# NRF9160.net
KiCad netlist of a schematic drawn in Altium Designer
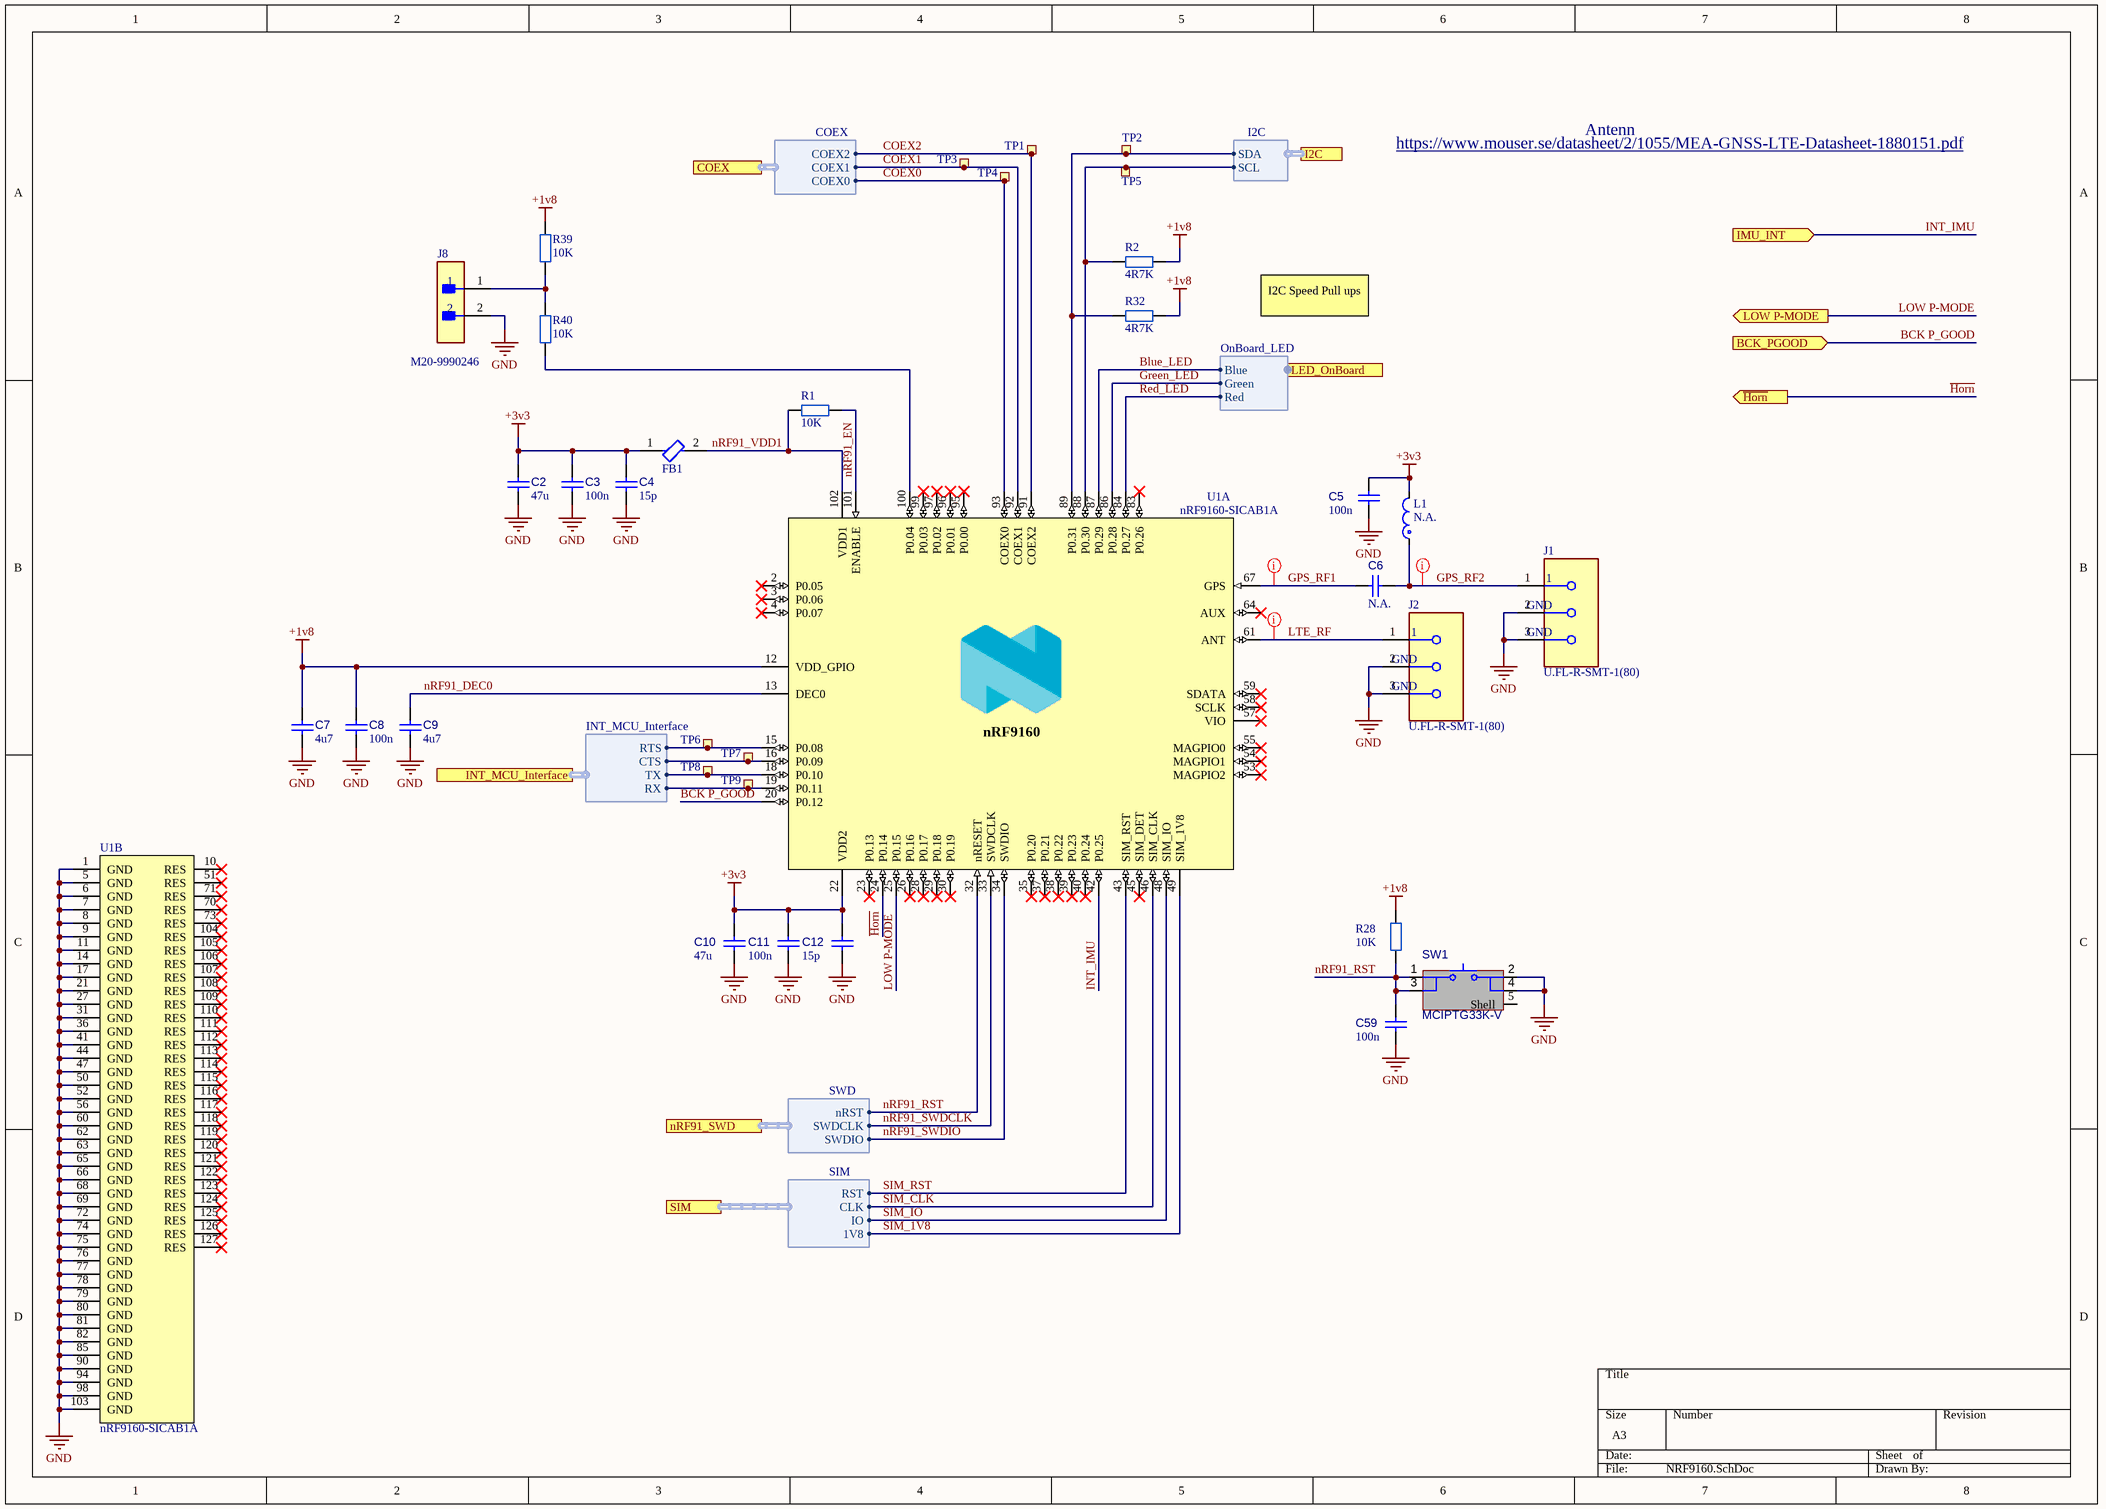
[diagram p0: NRF9160.SchDoc]

(export (version "E")
  (design (tool "Eeschema 10.0.6"))
  (components
    (comp (ref "C2")
      (value "47u")
      (footprint "CAPC2013X95X50LL10T25 HD")
      (description "Chip Capacitor, 0805 (2012 Metric)")
      (fields (field (name "TOLERANCE") "?%") (field (name "Comment") "Capacitor 0805"))
      (libsource (lib "Motonaut") (part "CAP-NP-2"))
    )
    (comp (ref "C3")
      (value "100n")
      (footprint "CAPC1005X55X25LL05T10 HD")
      (description "Chip Capacitor, 0402 (1005 Metric)")
      (fields (field (name "TOLERANCE") "?%") (field (name "Comment") "Capacitor 0402"))
      (libsource (lib "Motonaut") (part "CAP-NP-2"))
    )
    (comp (ref "C4")
      (value "15p")
      (footprint "CAPC1005X55X25LL05T10 HD")
      (description "Chip Capacitor, 0402 (1005 Metric)")
      (fields (field (name "TOLERANCE") "?%") (field (name "Comment") "Capacitor 0402"))
      (libsource (lib "Motonaut") (part "CAP-NP-2"))
    )
    (comp (ref "C5")
      (value "100n")
      (footprint "CAPC1005X55X25LL05T10 HD")
      (description "Chip Capacitor, 0402 (1005 Metric)")
      (fields (field (name "TOLERANCE") "?%") (field (name "Comment") "Capacitor 0402"))
      (libsource (lib "Motonaut") (part "CAP-NP-2"))
    )
    (comp (ref "C6")
      (value "N.A.")
      (footprint "CAPC1005X55X25LL05T10 HD")
      (description "Chip Capacitor, 0402 (1005 Metric)")
      (fields (field (name "TOLERANCE") "?%") (field (name "Comment") "Capacitor 0402"))
      (libsource (lib "Motonaut") (part "CAP-NP-2"))
    )
    (comp (ref "C7")
      (value "4u7")
      (footprint "CAPC1608X90X40LL10T20 HD")
      (description "Chip Capacitor, 0603 (1608 Metric)")
      (fields (field (name "TOLERANCE") "?%") (field (name "Comment") "Capacitor 0603"))
      (libsource (lib "Motonaut") (part "CAP-NP-2"))
    )
    (comp (ref "C8")
      (value "100n")
      (footprint "CAPC1005X55X25LL05T10 HD")
      (description "Chip Capacitor, 0402 (1005 Metric)")
      (fields (field (name "TOLERANCE") "?%") (field (name "Comment") "Capacitor 0402"))
      (libsource (lib "Motonaut") (part "CAP-NP-2"))
    )
    (comp (ref "C9")
      (value "4u7")
      (footprint "CAPC1608X90X40LL10T20 HD")
      (description "Chip Capacitor, 0603 (1608 Metric)")
      (fields (field (name "TOLERANCE") "?%") (field (name "Comment") "Capacitor 0603"))
      (libsource (lib "Motonaut") (part "CAP-NP-2"))
    )
    (comp (ref "C10")
      (value "47u")
      (footprint "CAPC2013X95X50LL10T25 HD")
      (description "Chip Capacitor, 0805 (2012 Metric)")
      (fields (field (name "TOLERANCE") "?%") (field (name "Comment") "Capacitor 0805"))
      (libsource (lib "Motonaut") (part "CAP-NP-2"))
    )
    (comp (ref "C11")
      (value "100n")
      (footprint "CAPC1005X55X25LL05T10 HD")
      (description "Chip Capacitor, 0402 (1005 Metric)")
      (fields (field (name "TOLERANCE") "?%") (field (name "Comment") "Capacitor 0402"))
      (libsource (lib "Motonaut") (part "CAP-NP-2"))
    )
    (comp (ref "C12")
      (value "15p")
      (footprint "CAPC1005X55X25LL05T10 HD")
      (description "Chip Capacitor, 0402 (1005 Metric)")
      (fields (field (name "TOLERANCE") "?%") (field (name "Comment") "Capacitor 0402"))
      (libsource (lib "Motonaut") (part "CAP-NP-2"))
    )
    (comp (ref "C59")
      (value "100n")
      (footprint "CAPC1005X55X25LL05T10 HD")
      (description "Chip Capacitor, 0402 (1005 Metric)")
      (fields (field (name "TOLERANCE") "?%") (field (name "Comment") "Capacitor 0402"))
      (libsource (lib "Motonaut") (part "CAP-NP-2"))
    )
    (comp (ref "FB1")
      (value "BLM15PX121SN1D")
      (footprint "FP-BLM15-0_05-d0_7-IPC_A")
      (description "Ferrite Beads Multi-Layer 120Ohm 25% 100MHz 2A 0.055Ohm DCR 0402 T/R")
      (libsource (lib "Motonaut") (part "5f30dd21d616792df468990f7003faa"))
    )
    (comp (ref "J1")
      (value "U.FL-R-SMT-1(80)")
      (footprint "FP-U_FL-R-SMT-1_80-MFG")
      (description "CONN U.FL RCPT STR 50 OHM SMD")
      (libsource (lib "Motonaut") (part "ad010367dc7cd7c7a13299a56582dd6"))
    )
    (comp (ref "J2")
      (value "U.FL-R-SMT-1(80)")
      (footprint "FP-U_FL-R-SMT-1_80-MFG")
      (description "CONN U.FL RCPT STR 50 OHM SMD")
      (libsource (lib "Motonaut") (part "ad010367dc7cd7c7a13299a56582dd6"))
    )
    (comp (ref "J8")
      (value "M20-9990246")
      (footprint "FP-M20-9990246-MFG")
      (description "CONN HEADER VERT 2POS 2.54MM")
      (fields
        (field (name "OCTOPART") "https://octopart.com/m20-9990246-harwin-2590635")
        (field (name "MANUFACTURER") "Harwin")
      )
      (libsource (lib "Altium Content Vault") (part "3bc925449376181038e59eaffc5286c"))
    )
    (comp (ref "L1")
      (value "N.A.")
      (footprint "INDC1005X55X25LL05T10_A")
      (description "Inductor RF Chip Thin Film 0402")
      (fields (field (name "Comment") "Inductor 0402"))
      (libsource (lib "Motonaut") (part "4cc4b267dca4c8e51f7102f422741d8"))
    )
    (comp (ref "R1")
      (value "10K")
      (footprint "RESC1005X40X25LL10T10 HD")
      (description "Resistor 0403")
      (libsource (lib "Motonaut") (part "Resistor EU"))
    )
    (comp (ref "R2")
      (value "4R7K")
      (footprint "RESC1005X40X25LL10T10 HD")
      (description "Resistor 0403")
      (libsource (lib "Motonaut") (part "Resistor EU"))
    )
    (comp (ref "R28")
      (value "10K")
      (footprint "RESC1005X40X25LL10T10 HD")
      (description "Resistor 0403")
      (libsource (lib "Motonaut") (part "Resistor EU"))
    )
    (comp (ref "R32")
      (value "4R7K")
      (footprint "RESC1005X40X25LL10T10 HD")
      (description "Resistor 0403")
      (libsource (lib "Motonaut") (part "Resistor EU"))
    )
    (comp (ref "R39")
      (value "10K")
      (footprint "RESC1005X40X25LL10T10 HD")
      (description "Resistor 0403")
      (libsource (lib "Motonaut") (part "Resistor EU"))
    )
    (comp (ref "R40")
      (value "10K")
      (footprint "RESC1005X40X25LL10T10 HD")
      (description "Resistor 0403")
      (libsource (lib "Motonaut") (part "Resistor EU"))
    )
    (comp (ref "SW1")
      (value "MCIPTG33K-V")
      (footprint "MCIPTG33K-V-Footprint-1")
      (libsource (lib "Motonaut") (part "4 pin button"))
    )
    (comp (ref "TP1")
      (value "TP_SMD_Ø0.7MM")
      (footprint "TP_SMD_Ø0.7mm")
      (description "0.7mm circular SMD testpad")
      (fields
        (field (name "MANUFACTURER") "Nordic Semiconductor")
        (field (name "MANUFACTURER PART NUMBER") "N.A.")
      )
      (libsource (lib "") (part "TP_SMD_Ø1.5MM_1"))
    )
    (comp (ref "TP2")
      (value "TP_SMD_Ø0.7MM")
      (footprint "TP_SMD_Ø0.7mm")
      (description "0.7mm circular SMD testpad")
      (fields
        (field (name "MANUFACTURER") "Nordic Semiconductor")
        (field (name "MANUFACTURER PART NUMBER") "N.A.")
      )
      (libsource (lib "") (part "TP_SMD_Ø1.5MM_1"))
    )
    (comp (ref "TP3")
      (value "TP_SMD_Ø0.7MM")
      (footprint "TP_SMD_Ø0.7mm")
      (description "0.7mm circular SMD testpad")
      (fields
        (field (name "MANUFACTURER") "Nordic Semiconductor")
        (field (name "MANUFACTURER PART NUMBER") "N.A.")
      )
      (libsource (lib "") (part "TP_SMD_Ø1.5MM_1"))
    )
    (comp (ref "TP4")
      (value "TP_SMD_Ø0.7MM")
      (footprint "TP_SMD_Ø0.7mm")
      (description "0.7mm circular SMD testpad")
      (fields
        (field (name "MANUFACTURER") "Nordic Semiconductor")
        (field (name "MANUFACTURER PART NUMBER") "N.A.")
      )
      (libsource (lib "") (part "TP_SMD_Ø1.5MM_1"))
    )
    (comp (ref "TP5")
      (value "TP_SMD_Ø0.7MM")
      (footprint "TP_SMD_Ø0.7mm")
      (description "0.7mm circular SMD testpad")
      (fields
        (field (name "MANUFACTURER") "Nordic Semiconductor")
        (field (name "MANUFACTURER PART NUMBER") "N.A.")
      )
      (libsource (lib "Motonaut") (part "TP_SMD_Ø1.5MM"))
    )
    (comp (ref "TP6")
      (value "TP_SMD_Ø0.7MM")
      (footprint "TP_SMD_Ø0.7mm")
      (description "0.7mm circular SMD testpad")
      (fields
        (field (name "MANUFACTURER") "Nordic Semiconductor")
        (field (name "MANUFACTURER PART NUMBER") "N.A.")
      )
      (libsource (lib "") (part "TP_SMD_Ø1.5MM_1"))
    )
    (comp (ref "TP7")
      (value "TP_SMD_Ø0.7MM")
      (footprint "TP_SMD_Ø0.7mm")
      (description "0.7mm circular SMD testpad")
      (fields
        (field (name "MANUFACTURER") "Nordic Semiconductor")
        (field (name "MANUFACTURER PART NUMBER") "N.A.")
      )
      (libsource (lib "") (part "TP_SMD_Ø1.5MM_1"))
    )
    (comp (ref "TP8")
      (value "TP_SMD_Ø0.7MM")
      (footprint "TP_SMD_Ø0.7mm")
      (description "0.7mm circular SMD testpad")
      (fields
        (field (name "MANUFACTURER") "Nordic Semiconductor")
        (field (name "MANUFACTURER PART NUMBER") "N.A.")
      )
      (libsource (lib "") (part "TP_SMD_Ø1.5MM_1"))
    )
    (comp (ref "TP9")
      (value "TP_SMD_Ø0.7MM")
      (footprint "TP_SMD_Ø0.7mm")
      (description "0.7mm circular SMD testpad")
      (fields
        (field (name "MANUFACTURER") "Nordic Semiconductor")
        (field (name "MANUFACTURER PART NUMBER") "N.A.")
      )
      (libsource (lib "") (part "TP_SMD_Ø1.5MM_1"))
    )
    (comp (ref "U1")
      (value "nRF9160-SICAB1A")
      (footprint "LGA50P1600X1050X104-161N")
      (description "Low power System-in-Package with integrated LTE-M/NB-IoT modem and GPS")
      (fields (field (name "MANUFACTURER") "Nordic Semiconductor"))
      (libsource (lib "Motonaut") (part "nRF9160-SICAB1A"))
    )
  )
  (nets
    (net (code "7") (name "+1v8") (class "Default")
      (node (ref "C7") (pin "2") (pinfunction "2_2") (pintype "passive"))
      (node (ref "C8") (pin "2") (pinfunction "2_2") (pintype "passive"))
      (node (ref "R2") (pin "2") (pinfunction "2_2") (pintype "passive"))
      (node (ref "R28") (pin "2") (pinfunction "2_2") (pintype "passive"))
      (node (ref "R32") (pin "2") (pinfunction "2_2") (pintype "passive"))
      (node (ref "R39") (pin "1") (pinfunction "1_1") (pintype "passive"))
      (node (ref "U1") (pin "12") (pinfunction "VDD_GPIO_12") (pintype "power_in"))
    )
    (net (code "8") (name "+3v3") (class "Default")
      (node (ref "C10") (pin "2") (pinfunction "2_2") (pintype "passive"))
      (node (ref "C11") (pin "2") (pinfunction "2_2") (pintype "passive"))
      (node (ref "C12") (pin "2") (pinfunction "2_2") (pintype "passive"))
      (node (ref "C2") (pin "2") (pinfunction "2_2") (pintype "passive"))
      (node (ref "C3") (pin "2") (pinfunction "2_2") (pintype "passive"))
      (node (ref "C4") (pin "2") (pinfunction "2_2") (pintype "passive"))
      (node (ref "C5") (pin "1") (pinfunction "1_1") (pintype "passive"))
      (node (ref "FB1") (pin "1") (pinfunction "1_1") (pintype "passive"))
      (node (ref "L1") (pin "2") (pinfunction "2_2") (pintype "passive"))
      (node (ref "U1") (pin "22") (pinfunction "VDD2_22") (pintype "power_in"))
    )
    (net (code "9") (name "/BCK P_GOOD") (class "Default")
      (node (ref "U1") (pin "20") (pinfunction "P0.12_20") (pintype "bidirectional"))
    )
    (net (code "10") (name "/Blue_LED") (class "Default")
      (node (ref "U1") (pin "87") (pinfunction "P0.29_87") (pintype "bidirectional"))
    )
    (net (code "11") (name "/COEX0") (class "Default")
      (node (ref "TP4") (pin "1") (pinfunction "1_1") (pintype "passive"))
      (node (ref "U1") (pin "93") (pinfunction "COEX0_93") (pintype "bidirectional"))
    )
    (net (code "12") (name "/COEX1") (class "Default")
      (node (ref "TP3") (pin "1") (pinfunction "1_1") (pintype "passive"))
      (node (ref "U1") (pin "92") (pinfunction "COEX1_92") (pintype "bidirectional"))
    )
    (net (code "13") (name "/COEX2") (class "Default")
      (node (ref "TP1") (pin "1") (pinfunction "1_1") (pintype "passive"))
      (node (ref "U1") (pin "91") (pinfunction "COEX2_91") (pintype "bidirectional"))
    )
    (net (code "14") (name "/GPS_RF1") (class "Default")
      (node (ref "C6") (pin "2") (pinfunction "2_2") (pintype "passive"))
      (node (ref "U1") (pin "67") (pinfunction "GPS_67") (pintype "input"))
    )
    (net (code "15") (name "/GPS_RF2") (class "Default")
      (node (ref "C6") (pin "1") (pinfunction "1_1") (pintype "passive"))
      (node (ref "J1") (pin "1") (pinfunction "1_1") (pintype "passive"))
      (node (ref "L1") (pin "1") (pinfunction "1_1") (pintype "passive"))
    )
    (net (code "16") (name "/Green_LED") (class "Default")
      (node (ref "U1") (pin "86") (pinfunction "P0.28_86") (pintype "bidirectional"))
    )
    (net (code "17") (name "/INT_IMU") (class "Default")
      (node (ref "U1") (pin "42") (pinfunction "P0.25_42") (pintype "bidirectional"))
    )
    (net (code "18") (name "/LOW P-MODE") (class "Default")
      (node (ref "U1") (pin "25") (pinfunction "P0.15_25") (pintype "bidirectional"))
    )
    (net (code "19") (name "/LTE_RF") (class "Default")
      (node (ref "J2") (pin "1") (pinfunction "1_1") (pintype "passive"))
      (node (ref "U1") (pin "61") (pinfunction "ANT_61") (pintype "bidirectional"))
    )
    (net (code "20") (name "/Red_LED") (class "Default")
      (node (ref "U1") (pin "84") (pinfunction "P0.27_84") (pintype "bidirectional"))
    )
    (net (code "21") (name "/SIM_1V8") (class "Default")
      (node (ref "U1") (pin "49") (pinfunction "SIM_1V8_49") (pintype "power_in"))
    )
    (net (code "22") (name "/SIM_CLK") (class "Default")
      (node (ref "U1") (pin "46") (pinfunction "SIM_CLK_46") (pintype "bidirectional"))
    )
    (net (code "23") (name "/SIM_IO") (class "Default")
      (node (ref "U1") (pin "48") (pinfunction "SIM_IO_48") (pintype "bidirectional"))
    )
    (net (code "24") (name "/SIM_RST") (class "Default")
      (node (ref "U1") (pin "43") (pinfunction "SIM_RST_43") (pintype "bidirectional"))
    )
    (net (code "25") (name "/nRF91_DEC0") (class "Default")
      (node (ref "C9") (pin "2") (pinfunction "2_2") (pintype "passive"))
      (node (ref "U1") (pin "13") (pinfunction "DEC0_13") (pintype "power_in"))
    )
    (net (code "26") (name "/nRF91_EN") (class "Default")
      (node (ref "R1") (pin "1") (pinfunction "1_1") (pintype "passive"))
      (node (ref "U1") (pin "101") (pinfunction "ENABLE_101") (pintype "input"))
    )
    (net (code "27") (name "/nRF91_RST") (class "Default")
      (node (ref "C59") (pin "2") (pinfunction "2_2") (pintype "passive"))
      (node (ref "R28") (pin "1") (pinfunction "1_1") (pintype "passive"))
      (node (ref "SW1") (pin "1") (pinfunction "1_1") (pintype "passive"))
      (node (ref "SW1") (pin "3") (pinfunction "3_3") (pintype "passive"))
      (node (ref "U1") (pin "32") (pinfunction "nRESET_32") (pintype "input"))
    )
    (net (code "28") (name "/nRF91_SWDCLK") (class "Default")
      (node (ref "U1") (pin "33") (pinfunction "SWDCLK_33") (pintype "input"))
    )
    (net (code "29") (name "/nRF91_SWDIO") (class "Default")
      (node (ref "U1") (pin "34") (pinfunction "SWDIO_34") (pintype "bidirectional"))
    )
    (net (code "30") (name "/nRF91_VDD1") (class "Default")
      (node (ref "FB1") (pin "2") (pinfunction "2_2") (pintype "passive"))
      (node (ref "R1") (pin "2") (pinfunction "2_2") (pintype "passive"))
      (node (ref "U1") (pin "102") (pinfunction "VDD1_102") (pintype "power_in"))
    )
    (net (code "37") (name "/~{Horn}") (class "Default")
      (node (ref "U1") (pin "24") (pinfunction "P0.14_24") (pintype "bidirectional"))
    )
    (net (code "38") (name "GND") (class "Default")
      (node (ref "C10") (pin "1") (pinfunction "1_1") (pintype "passive"))
      (node (ref "C11") (pin "1") (pinfunction "1_1") (pintype "passive"))
      (node (ref "C12") (pin "1") (pinfunction "1_1") (pintype "passive"))
      (node (ref "C2") (pin "1") (pinfunction "1_1") (pintype "passive"))
      (node (ref "C3") (pin "1") (pinfunction "1_1") (pintype "passive"))
      (node (ref "C4") (pin "1") (pinfunction "1_1") (pintype "passive"))
      (node (ref "C5") (pin "2") (pinfunction "2_2") (pintype "passive"))
      (node (ref "C59") (pin "1") (pinfunction "1_1") (pintype "passive"))
      (node (ref "C7") (pin "1") (pinfunction "1_1") (pintype "passive"))
      (node (ref "C8") (pin "1") (pinfunction "1_1") (pintype "passive"))
      (node (ref "C9") (pin "1") (pinfunction "1_1") (pintype "passive"))
      (node (ref "J1") (pin "2") (pinfunction "GND_2") (pintype "power_in"))
      (node (ref "J1") (pin "3") (pinfunction "GND_3") (pintype "power_in"))
      (node (ref "J2") (pin "2") (pinfunction "GND_2") (pintype "power_in"))
      (node (ref "J2") (pin "3") (pinfunction "GND_3") (pintype "power_in"))
      (node (ref "J8") (pin "2") (pinfunction "2_2") (pintype "passive"))
      (node (ref "SW1") (pin "2") (pinfunction "2_2") (pintype "passive"))
      (node (ref "SW1") (pin "4") (pinfunction "4_4") (pintype "passive"))
      (node (ref "U1") (pin "1") (pinfunction "GND_1") (pintype "power_in"))
      (node (ref "U1") (pin "103") (pinfunction "GND_103") (pintype "power_in"))
      (node (ref "U1") (pin "11") (pinfunction "GND_11") (pintype "passive"))
      (node (ref "U1") (pin "14") (pinfunction "GND_14") (pintype "power_in"))
      (node (ref "U1") (pin "17") (pinfunction "GND_17") (pintype "power_in"))
      (node (ref "U1") (pin "21") (pinfunction "GND_21") (pintype "power_in"))
      (node (ref "U1") (pin "27") (pinfunction "GND_27") (pintype "power_in"))
      (node (ref "U1") (pin "31") (pinfunction "GND_31") (pintype "power_in"))
      (node (ref "U1") (pin "36") (pinfunction "GND_36") (pintype "power_in"))
      (node (ref "U1") (pin "41") (pinfunction "GND_41") (pintype "power_in"))
      (node (ref "U1") (pin "44") (pinfunction "GND_44") (pintype "power_in"))
      (node (ref "U1") (pin "47") (pinfunction "GND_47") (pintype "power_in"))
      (node (ref "U1") (pin "5") (pinfunction "GND_5") (pintype "power_in"))
      (node (ref "U1") (pin "50") (pinfunction "GND_50") (pintype "power_in"))
      (node (ref "U1") (pin "52") (pinfunction "GND_52") (pintype "power_in"))
      (node (ref "U1") (pin "56") (pinfunction "GND_56") (pintype "power_in"))
      (node (ref "U1") (pin "6") (pinfunction "GND_6") (pintype "passive"))
      (node (ref "U1") (pin "60") (pinfunction "GND_60") (pintype "power_in"))
      (node (ref "U1") (pin "62") (pinfunction "GND_62") (pintype "power_in"))
      (node (ref "U1") (pin "63") (pinfunction "GND_63") (pintype "power_in"))
      (node (ref "U1") (pin "65") (pinfunction "GND_65") (pintype "power_in"))
      (node (ref "U1") (pin "66") (pinfunction "GND_66") (pintype "power_in"))
      (node (ref "U1") (pin "68") (pinfunction "GND_68") (pintype "passive"))
      (node (ref "U1") (pin "69") (pinfunction "GND_69") (pintype "passive"))
      (node (ref "U1") (pin "7") (pinfunction "GND_7") (pintype "passive"))
      (node (ref "U1") (pin "72") (pinfunction "GND_72") (pintype "power_in"))
      (node (ref "U1") (pin "74") (pinfunction "GND_74") (pintype "power_in"))
      (node (ref "U1") (pin "75") (pinfunction "GND_75") (pintype "power_in"))
      (node (ref "U1") (pin "76") (pinfunction "GND_76") (pintype "power_in"))
      (node (ref "U1") (pin "77") (pinfunction "GND_77") (pintype "power_in"))
      (node (ref "U1") (pin "78") (pinfunction "GND_78") (pintype "power_in"))
      (node (ref "U1") (pin "79") (pinfunction "GND_79") (pintype "power_in"))
      (node (ref "U1") (pin "8") (pinfunction "GND_8") (pintype "passive"))
      (node (ref "U1") (pin "80") (pinfunction "GND_80") (pintype "power_in"))
      (node (ref "U1") (pin "81") (pinfunction "GND_81") (pintype "power_in"))
      (node (ref "U1") (pin "82") (pinfunction "GND_82") (pintype "power_in"))
      (node (ref "U1") (pin "85") (pinfunction "GND_85") (pintype "power_in"))
      (node (ref "U1") (pin "9") (pinfunction "GND_9") (pintype "power_in"))
      (node (ref "U1") (pin "90") (pinfunction "GND_90") (pintype "power_in"))
      (node (ref "U1") (pin "94") (pinfunction "GND_94") (pintype "power_in"))
      (node (ref "U1") (pin "98") (pinfunction "GND_98") (pintype "power_in"))
    )
    (net (code "39") (name "Net-(J8-Pad1)") (class "Default")
      (node (ref "J8") (pin "1") (pinfunction "1_1") (pintype "passive"))
      (node (ref "R39") (pin "2") (pinfunction "2_2") (pintype "passive"))
      (node (ref "R40") (pin "2") (pinfunction "2_2") (pintype "passive"))
    )
    (net (code "40") (name "Net-(U1A-P0.04)") (class "Default")
      (node (ref "R40") (pin "1") (pinfunction "1_1") (pintype "passive"))
      (node (ref "U1") (pin "100") (pinfunction "P0.04_100") (pintype "bidirectional"))
    )
    (net (code "41") (name "Net-(U1A-P0.08)") (class "Default")
      (node (ref "TP6") (pin "1") (pinfunction "1_1") (pintype "passive"))
      (node (ref "U1") (pin "15") (pinfunction "P0.08_15") (pintype "bidirectional"))
    )
    (net (code "42") (name "Net-(U1A-P0.09)") (class "Default")
      (node (ref "TP7") (pin "1") (pinfunction "1_1") (pintype "passive"))
      (node (ref "U1") (pin "16") (pinfunction "P0.09_16") (pintype "bidirectional"))
    )
    (net (code "43") (name "Net-(U1A-P0.10)") (class "Default")
      (node (ref "TP8") (pin "1") (pinfunction "1_1") (pintype "passive"))
      (node (ref "U1") (pin "18") (pinfunction "P0.10_18") (pintype "bidirectional"))
    )
    (net (code "44") (name "Net-(U1A-P0.11)") (class "Default")
      (node (ref "TP9") (pin "1") (pinfunction "1_1") (pintype "passive"))
      (node (ref "U1") (pin "19") (pinfunction "P0.11_19") (pintype "bidirectional"))
    )
    (net (code "45") (name "Net-(U1A-P0.30)") (class "Default")
      (node (ref "R2") (pin "1") (pinfunction "1_1") (pintype "passive"))
      (node (ref "TP5") (pin "1") (pinfunction "1_1") (pintype "passive"))
      (node (ref "U1") (pin "88") (pinfunction "P0.30_88") (pintype "bidirectional"))
    )
    (net (code "46") (name "Net-(U1A-P0.31)") (class "Default")
      (node (ref "R32") (pin "1") (pinfunction "1_1") (pintype "passive"))
      (node (ref "TP2") (pin "1") (pinfunction "1_1") (pintype "passive"))
      (node (ref "U1") (pin "89") (pinfunction "P0.31_89") (pintype "bidirectional"))
    )
    (net (code "47") (name "unconnected-(SW1-Shell-Pad5)") (class "Default")
      (node (ref "SW1") (pin "5") (pinfunction "Shell_5") (pintype "passive"))
    )
    (net (code "48") (name "unconnected-(U1A-AUX-Pad64)") (class "Default")
      (node (ref "U1") (pin "64") (pinfunction "AUX_64") (pintype "bidirectional+no_connect"))
    )
    (net (code "49") (name "unconnected-(U1A-MAGPIO0-Pad55)") (class "Default")
      (node (ref "U1") (pin "55") (pinfunction "MAGPIO0_55") (pintype "bidirectional+no_connect"))
    )
    (net (code "50") (name "unconnected-(U1A-MAGPIO1-Pad54)") (class "Default")
      (node (ref "U1") (pin "54") (pinfunction "MAGPIO1_54") (pintype "bidirectional+no_connect"))
    )
    (net (code "51") (name "unconnected-(U1A-MAGPIO2-Pad53)") (class "Default")
      (node (ref "U1") (pin "53") (pinfunction "MAGPIO2_53") (pintype "bidirectional+no_connect"))
    )
    (net (code "52") (name "unconnected-(U1A-P0.00-Pad95)") (class "Default")
      (node (ref "U1") (pin "95") (pinfunction "P0.00_95") (pintype "bidirectional+no_connect"))
    )
    (net (code "53") (name "unconnected-(U1A-P0.01-Pad96)") (class "Default")
      (node (ref "U1") (pin "96") (pinfunction "P0.01_96") (pintype "bidirectional+no_connect"))
    )
    (net (code "54") (name "unconnected-(U1A-P0.02-Pad97)") (class "Default")
      (node (ref "U1") (pin "97") (pinfunction "P0.02_97") (pintype "bidirectional+no_connect"))
    )
    (net (code "55") (name "unconnected-(U1A-P0.03-Pad99)") (class "Default")
      (node (ref "U1") (pin "99") (pinfunction "P0.03_99") (pintype "bidirectional+no_connect"))
    )
    (net (code "56") (name "unconnected-(U1A-P0.05-Pad2)") (class "Default")
      (node (ref "U1") (pin "2") (pinfunction "P0.05_2") (pintype "bidirectional+no_connect"))
    )
    (net (code "57") (name "unconnected-(U1A-P0.06-Pad3)") (class "Default")
      (node (ref "U1") (pin "3") (pinfunction "P0.06_3") (pintype "bidirectional+no_connect"))
    )
    (net (code "58") (name "unconnected-(U1A-P0.07-Pad4)") (class "Default")
      (node (ref "U1") (pin "4") (pinfunction "P0.07_4") (pintype "bidirectional+no_connect"))
    )
    (net (code "59") (name "unconnected-(U1A-P0.13-Pad23)") (class "Default")
      (node (ref "U1") (pin "23") (pinfunction "P0.13_23") (pintype "bidirectional+no_connect"))
    )
    (net (code "60") (name "unconnected-(U1A-P0.16-Pad26)") (class "Default")
      (node (ref "U1") (pin "26") (pinfunction "P0.16_26") (pintype "bidirectional+no_connect"))
    )
    (net (code "61") (name "unconnected-(U1A-P0.17-Pad28)") (class "Default")
      (node (ref "U1") (pin "28") (pinfunction "P0.17_28") (pintype "bidirectional+no_connect"))
    )
    (net (code "62") (name "unconnected-(U1A-P0.18-Pad29)") (class "Default")
      (node (ref "U1") (pin "29") (pinfunction "P0.18_29") (pintype "bidirectional+no_connect"))
    )
    (net (code "63") (name "unconnected-(U1A-P0.19-Pad30)") (class "Default")
      (node (ref "U1") (pin "30") (pinfunction "P0.19_30") (pintype "bidirectional+no_connect"))
    )
    (net (code "64") (name "unconnected-(U1A-P0.20-Pad35)") (class "Default")
      (node (ref "U1") (pin "35") (pinfunction "P0.20_35") (pintype "bidirectional+no_connect"))
    )
    (net (code "65") (name "unconnected-(U1A-P0.21-Pad37)") (class "Default")
      (node (ref "U1") (pin "37") (pinfunction "P0.21_37") (pintype "bidirectional+no_connect"))
    )
    (net (code "66") (name "unconnected-(U1A-P0.22-Pad38)") (class "Default")
      (node (ref "U1") (pin "38") (pinfunction "P0.22_38") (pintype "bidirectional+no_connect"))
    )
    (net (code "67") (name "unconnected-(U1A-P0.23-Pad39)") (class "Default")
      (node (ref "U1") (pin "39") (pinfunction "P0.23_39") (pintype "bidirectional+no_connect"))
    )
    (net (code "68") (name "unconnected-(U1A-P0.24-Pad40)") (class "Default")
      (node (ref "U1") (pin "40") (pinfunction "P0.24_40") (pintype "bidirectional+no_connect"))
    )
    (net (code "69") (name "unconnected-(U1A-P0.26-Pad83)") (class "Default")
      (node (ref "U1") (pin "83") (pinfunction "P0.26_83") (pintype "bidirectional+no_connect"))
    )
    (net (code "70") (name "unconnected-(U1A-SCLK-Pad58)") (class "Default")
      (node (ref "U1") (pin "58") (pinfunction "SCLK_58") (pintype "bidirectional+no_connect"))
    )
    (net (code "71") (name "unconnected-(U1A-SDATA-Pad59)") (class "Default")
      (node (ref "U1") (pin "59") (pinfunction "SDATA_59") (pintype "bidirectional+no_connect"))
    )
    (net (code "72") (name "unconnected-(U1A-SIM_DET-Pad45)") (class "Default")
      (node (ref "U1") (pin "45") (pinfunction "SIM_DET_45") (pintype "bidirectional+no_connect"))
    )
    (net (code "73") (name "unconnected-(U1A-VIO-Pad57)") (class "Default")
      (node (ref "U1") (pin "57") (pinfunction "VIO_57") (pintype "power_in+no_connect"))
    )
    (net (code "74") (name "unconnected-(U1B-RES-Pad10)") (class "Default")
      (node (ref "U1") (pin "10") (pinfunction "RES_10") (pintype "passive+no_connect"))
    )
    (net (code "75") (name "unconnected-(U1B-RES-Pad51)") (class "Default")
      (node (ref "U1") (pin "51") (pinfunction "RES_51") (pintype "passive+no_connect"))
    )
    (net (code "76") (name "unconnected-(U1B-RES-Pad70)") (class "Default")
      (node (ref "U1") (pin "70") (pinfunction "RES_70") (pintype "passive+no_connect"))
    )
    (net (code "77") (name "unconnected-(U1B-RES-Pad71)") (class "Default")
      (node (ref "U1") (pin "71") (pinfunction "RES_71") (pintype "passive+no_connect"))
    )
    (net (code "78") (name "unconnected-(U1B-RES-Pad73)") (class "Default")
      (node (ref "U1") (pin "73") (pinfunction "RES_73") (pintype "passive+no_connect"))
    )
    (net (code "79") (name "unconnected-(U1B-RES-Pad104)") (class "Default")
      (node (ref "U1") (pin "104") (pinfunction "RES_104") (pintype "passive+no_connect"))
    )
    (net (code "80") (name "unconnected-(U1B-RES-Pad105)") (class "Default")
      (node (ref "U1") (pin "105") (pinfunction "RES_105") (pintype "passive+no_connect"))
    )
    (net (code "81") (name "unconnected-(U1B-RES-Pad106)") (class "Default")
      (node (ref "U1") (pin "106") (pinfunction "RES_106") (pintype "passive+no_connect"))
    )
    (net (code "82") (name "unconnected-(U1B-RES-Pad107)") (class "Default")
      (node (ref "U1") (pin "107") (pinfunction "RES_107") (pintype "passive+no_connect"))
    )
    (net (code "83") (name "unconnected-(U1B-RES-Pad108)") (class "Default")
      (node (ref "U1") (pin "108") (pinfunction "RES_108") (pintype "passive+no_connect"))
    )
    (net (code "84") (name "unconnected-(U1B-RES-Pad109)") (class "Default")
      (node (ref "U1") (pin "109") (pinfunction "RES_109") (pintype "passive+no_connect"))
    )
    (net (code "85") (name "unconnected-(U1B-RES-Pad110)") (class "Default")
      (node (ref "U1") (pin "110") (pinfunction "RES_110") (pintype "passive+no_connect"))
    )
    (net (code "86") (name "unconnected-(U1B-RES-Pad111)") (class "Default")
      (node (ref "U1") (pin "111") (pinfunction "RES_111") (pintype "passive+no_connect"))
    )
    (net (code "87") (name "unconnected-(U1B-RES-Pad112)") (class "Default")
      (node (ref "U1") (pin "112") (pinfunction "RES_112") (pintype "passive+no_connect"))
    )
    (net (code "88") (name "unconnected-(U1B-RES-Pad113)") (class "Default")
      (node (ref "U1") (pin "113") (pinfunction "RES_113") (pintype "passive+no_connect"))
    )
    (net (code "89") (name "unconnected-(U1B-RES-Pad114)") (class "Default")
      (node (ref "U1") (pin "114") (pinfunction "RES_114") (pintype "passive+no_connect"))
    )
    (net (code "90") (name "unconnected-(U1B-RES-Pad115)") (class "Default")
      (node (ref "U1") (pin "115") (pinfunction "RES_115") (pintype "passive+no_connect"))
    )
    (net (code "91") (name "unconnected-(U1B-RES-Pad116)") (class "Default")
      (node (ref "U1") (pin "116") (pinfunction "RES_116") (pintype "passive+no_connect"))
    )
    (net (code "92") (name "unconnected-(U1B-RES-Pad117)") (class "Default")
      (node (ref "U1") (pin "117") (pinfunction "RES_117") (pintype "passive+no_connect"))
    )
    (net (code "93") (name "unconnected-(U1B-RES-Pad118)") (class "Default")
      (node (ref "U1") (pin "118") (pinfunction "RES_118") (pintype "passive+no_connect"))
    )
    (net (code "94") (name "unconnected-(U1B-RES-Pad119)") (class "Default")
      (node (ref "U1") (pin "119") (pinfunction "RES_119") (pintype "passive+no_connect"))
    )
    (net (code "95") (name "unconnected-(U1B-RES-Pad120)") (class "Default")
      (node (ref "U1") (pin "120") (pinfunction "RES_120") (pintype "passive+no_connect"))
    )
    (net (code "96") (name "unconnected-(U1B-RES-Pad121)") (class "Default")
      (node (ref "U1") (pin "121") (pinfunction "RES_121") (pintype "passive+no_connect"))
    )
    (net (code "97") (name "unconnected-(U1B-RES-Pad122)") (class "Default")
      (node (ref "U1") (pin "122") (pinfunction "RES_122") (pintype "passive+no_connect"))
    )
    (net (code "98") (name "unconnected-(U1B-RES-Pad123)") (class "Default")
      (node (ref "U1") (pin "123") (pinfunction "RES_123") (pintype "passive+no_connect"))
    )
    (net (code "99") (name "unconnected-(U1B-RES-Pad124)") (class "Default")
      (node (ref "U1") (pin "124") (pinfunction "RES_124") (pintype "passive+no_connect"))
    )
    (net (code "100") (name "unconnected-(U1B-RES-Pad125)") (class "Default")
      (node (ref "U1") (pin "125") (pinfunction "RES_125") (pintype "passive+no_connect"))
    )
    (net (code "101") (name "unconnected-(U1B-RES-Pad126)") (class "Default")
      (node (ref "U1") (pin "126") (pinfunction "RES_126") (pintype "passive+no_connect"))
    )
    (net (code "102") (name "unconnected-(U1B-RES-Pad127)") (class "Default")
      (node (ref "U1") (pin "127") (pinfunction "RES_127") (pintype "passive+no_connect"))
    )
  )
)
